# IronBen.net
KiCad netlist of a schematic drawn in EasyEDA Pro
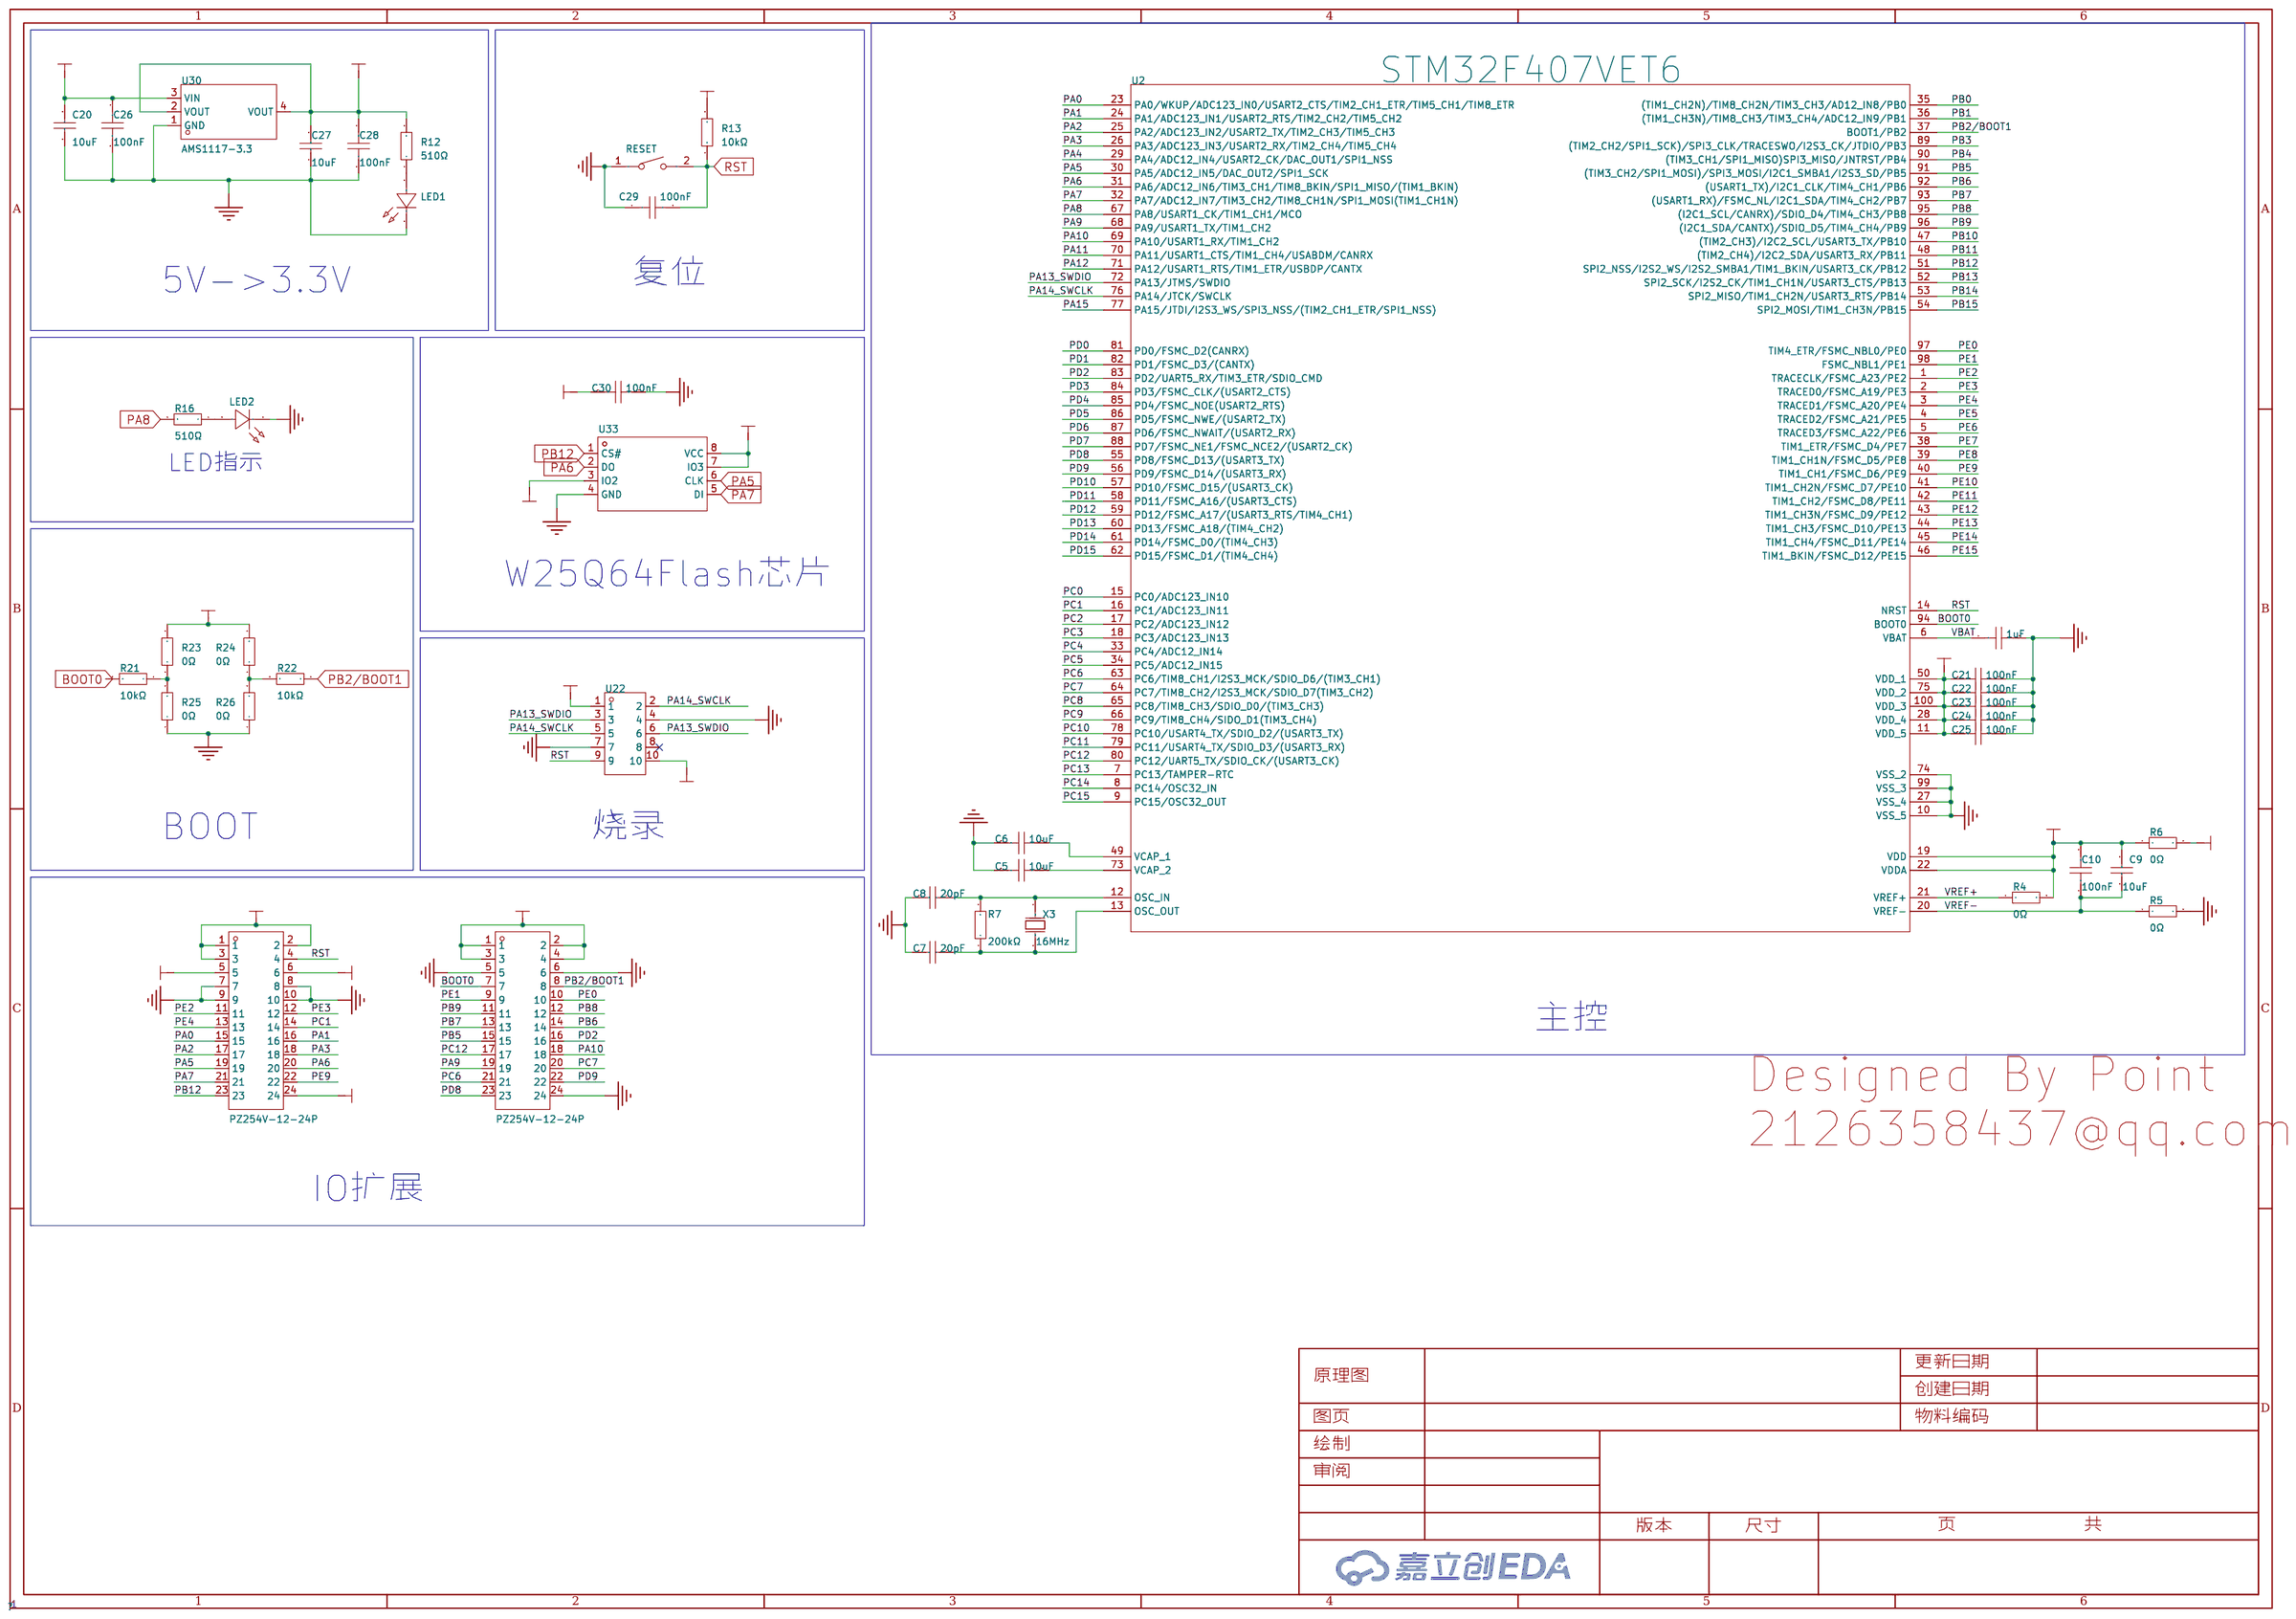
[diagram p0: schematic sheet]

(export (version "E")
  (design (tool "Eeschema 10.0.6"))
  (components
    (comp (ref "C5")
      (value "10uF")
      (footprint "easyedapro:C0603")
      (description "容值:10uF;精度:±10%;额定电压:10V;材质(温度系数):X5R;")
      (fields
        (field (name "Manufacturer Part") "CL10A106KP8NNNC")
        (field (name "Manufacturer") "SAMSUNG(三星)")
      )
      (libsource (lib "easyedapro") (part "CL10A106KP8NNNC"))
    )
    (comp (ref "C6")
      (value "10uF")
      (footprint "easyedapro:C0603")
      (description "容值:10uF;精度:±10%;额定电压:10V;材质(温度系数):X5R;")
      (fields
        (field (name "Manufacturer Part") "CL10A106KP8NNNC")
        (field (name "Manufacturer") "SAMSUNG(三星)")
      )
      (libsource (lib "easyedapro") (part "CL10A106KP8NNNC"))
    )
    (comp (ref "C7")
      (value "20pF")
      (footprint "easyedapro:C0603")
      (description "容值:20pF;精度:±5%;额定电压:50V;材质(温度系数):C0G;")
      (fields
        (field (name "Manufacturer Part") "CL10C200JB8NNNC")
        (field (name "Manufacturer") "SAMSUNG(三星)")
      )
      (libsource (lib "easyedapro") (part "CL10C200JB8NNNC"))
    )
    (comp (ref "C8")
      (value "20pF")
      (footprint "easyedapro:C0603")
      (description "容值:20pF;精度:±5%;额定电压:50V;材质(温度系数):C0G;")
      (fields
        (field (name "Manufacturer Part") "CL10C200JB8NNNC")
        (field (name "Manufacturer") "SAMSUNG(三星)")
      )
      (libsource (lib "easyedapro") (part "CL10C200JB8NNNC"))
    )
    (comp (ref "C9")
      (value "10uF")
      (footprint "easyedapro:C0805")
      (description "容值:10uF;精度:±10%;额定电压:10V;材质(温度系数):X5R;")
      (fields
        (field (name "Manufacturer Part") "CL21A106KPFNNNE")
        (field (name "Manufacturer") "SAMSUNG(三星)")
      )
      (libsource (lib "easyedapro") (part "CL21A106KPFNNNE"))
    )
    (comp (ref "C10")
      (value "100nF")
      (footprint "easyedapro:C0603")
      (description "容值:100nF;精度:±10%;额定电压:50V;材质(温度系数):X7R;")
      (fields
        (field (name "Manufacturer Part") "CC0603KRX7R9BB104")
        (field (name "Manufacturer") "YAGEO(国巨)")
      )
      (libsource (lib "easyedapro") (part "CC0603KRX7R9BB104"))
    )
    (comp (ref "C11")
      (value "1uF")
      (footprint "easyedapro:C0603")
      (description "容值:1uF;精度:±10%;额定电压:50V;材质(温度系数):X5R;")
      (fields
        (field (name "Manufacturer Part") "CL10A105KB8NNNC")
        (field (name "Manufacturer") "SAMSUNG(三星)")
      )
      (libsource (lib "easyedapro") (part "CL10A105KB8NNNC"))
    )
    (comp (ref "C20")
      (value "10uF")
      (footprint "easyedapro:C0805")
      (description "容值:10uF;精度:±10%;额定电压:10V;材质(温度系数):X5R;")
      (fields
        (field (name "Manufacturer Part") "CL21A106KPFNNNE")
        (field (name "Manufacturer") "SAMSUNG(三星)")
      )
      (libsource (lib "easyedapro") (part "CL21A106KPFNNNE"))
    )
    (comp (ref "C21")
      (value "100nF")
      (footprint "easyedapro:C0603")
      (description "容值:100nF;精度:±10%;额定电压:50V;材质(温度系数):X7R;")
      (fields
        (field (name "Manufacturer Part") "CC0603KRX7R9BB104")
        (field (name "Manufacturer") "YAGEO(国巨)")
      )
      (libsource (lib "easyedapro") (part "CC0603KRX7R9BB104"))
    )
    (comp (ref "C22")
      (value "100nF")
      (footprint "easyedapro:C0603")
      (description "容值:100nF;精度:±10%;额定电压:50V;材质(温度系数):X7R;")
      (fields
        (field (name "Manufacturer Part") "CC0603KRX7R9BB104")
        (field (name "Manufacturer") "YAGEO(国巨)")
      )
      (libsource (lib "easyedapro") (part "CC0603KRX7R9BB104"))
    )
    (comp (ref "C23")
      (value "100nF")
      (footprint "easyedapro:C0603")
      (description "容值:100nF;精度:±10%;额定电压:50V;材质(温度系数):X7R;")
      (fields
        (field (name "Manufacturer Part") "CC0603KRX7R9BB104")
        (field (name "Manufacturer") "YAGEO(国巨)")
      )
      (libsource (lib "easyedapro") (part "CC0603KRX7R9BB104"))
    )
    (comp (ref "C24")
      (value "100nF")
      (footprint "easyedapro:C0603")
      (description "容值:100nF;精度:±10%;额定电压:50V;材质(温度系数):X7R;")
      (fields
        (field (name "Manufacturer Part") "CC0603KRX7R9BB104")
        (field (name "Manufacturer") "YAGEO(国巨)")
      )
      (libsource (lib "easyedapro") (part "CC0603KRX7R9BB104"))
    )
    (comp (ref "C25")
      (value "100nF")
      (footprint "easyedapro:C0603")
      (description "容值:100nF;精度:±10%;额定电压:50V;材质(温度系数):X7R;")
      (fields
        (field (name "Manufacturer Part") "CC0603KRX7R9BB104")
        (field (name "Manufacturer") "YAGEO(国巨)")
      )
      (libsource (lib "easyedapro") (part "CC0603KRX7R9BB104"))
    )
    (comp (ref "C26")
      (value "100nF")
      (footprint "easyedapro:C0603")
      (description "容值:100nF;精度:±10%;额定电压:50V;材质(温度系数):X7R;")
      (fields
        (field (name "Manufacturer Part") "CC0603KRX7R9BB104")
        (field (name "Manufacturer") "YAGEO(国巨)")
      )
      (libsource (lib "easyedapro") (part "CC0603KRX7R9BB104"))
    )
    (comp (ref "C27")
      (value "10uF")
      (footprint "easyedapro:C0805")
      (description "容值:10uF;精度:±10%;额定电压:10V;材质(温度系数):X5R;")
      (fields
        (field (name "Manufacturer Part") "CL21A106KPFNNNE")
        (field (name "Manufacturer") "SAMSUNG(三星)")
      )
      (libsource (lib "easyedapro") (part "CL21A106KPFNNNE"))
    )
    (comp (ref "C28")
      (value "100nF")
      (footprint "easyedapro:C0603")
      (description "容值:100nF;精度:±10%;额定电压:50V;材质(温度系数):X7R;")
      (fields
        (field (name "Manufacturer Part") "CC0603KRX7R9BB104")
        (field (name "Manufacturer") "YAGEO(国巨)")
      )
      (libsource (lib "easyedapro") (part "CC0603KRX7R9BB104"))
    )
    (comp (ref "C29")
      (value "100nF")
      (footprint "easyedapro:C0603")
      (description "容值:100nF;精度:±10%;额定电压:50V;材质(温度系数):X7R;")
      (fields
        (field (name "Manufacturer Part") "CC0603KRX7R9BB104")
        (field (name "Manufacturer") "YAGEO(国巨)")
      )
      (libsource (lib "easyedapro") (part "CC0603KRX7R9BB104"))
    )
    (comp (ref "C30")
      (value "100nF")
      (footprint "easyedapro:C0603")
      (description "容值:100nF;精度:±10%;额定电压:50V;材质(温度系数):X7R;")
      (fields
        (field (name "Manufacturer Part") "CC0603KRX7R9BB104")
        (field (name "Manufacturer") "YAGEO(国巨)")
      )
      (libsource (lib "easyedapro") (part "CC0603KRX7R9BB104"))
    )
    (comp (ref "H6")
      (value "PZ254V-12-24P")
      (footprint "easyedapro:HDR-TH_24P-P2.54-V-M-R2-C12-S2.54")
      (fields (field (name "Manufacturer") "XFCN(兴飞)"))
      (libsource (lib "easyedapro") (part "PZ254V-12-24P"))
    )
    (comp (ref "H7")
      (value "PZ254V-12-24P")
      (footprint "easyedapro:HDR-TH_24P-P2.54-V-M-R2-C12-S2.54")
      (fields (field (name "Manufacturer") "XFCN(兴飞)"))
      (libsource (lib "easyedapro") (part "PZ254V-12-24P"))
    )
    (comp (ref "LED1")
      (value "XL-1608SURC-06")
      (footprint "easyedapro:LED0603-RD_RED")
      (description "发光颜色:红色;功率:55mW;正向电流:25mA;主波长:617nm~621nm;透镜颜色:无色透明透镜;色温:-;发光角度:120°;载带方式:正贴;工作温度:-30°C~+85°C;")
      (fields (field (name "Manufacturer") "XINGLIGHT(成兴光)"))
      (libsource (lib "easyedapro") (part "XL-1608SURC-06"))
    )
    (comp (ref "LED2")
      (value "XL-1608SURC-06")
      (footprint "easyedapro:LED0603-RD_RED")
      (description "发光颜色:红色;功率:55mW;正向电流:25mA;主波长:617nm~621nm;透镜颜色:无色透明透镜;色温:-;发光角度:120°;载带方式:正贴;工作温度:-30°C~+85°C;")
      (fields (field (name "Manufacturer") "XINGLIGHT(成兴光)"))
      (libsource (lib "easyedapro") (part "XL-1608SURC-06"))
    )
    (comp (ref "R4")
      (value "0Ω")
      (footprint "easyedapro:R0603")
      (description "电阻类型:厚膜电阻;阻值:0Ω;精度:±1%;功率:100mW;最大工作电压:75V;")
      (fields
        (field (name "Manufacturer Part") "0603WAF0000T5E")
        (field (name "Manufacturer") "UNI-ROYAL(厚声)")
      )
      (libsource (lib "easyedapro") (part "0603WAF0000T5E"))
    )
    (comp (ref "R5")
      (value "0Ω")
      (footprint "easyedapro:R0603")
      (description "电阻类型:厚膜电阻;阻值:0Ω;精度:±1%;功率:100mW;最大工作电压:75V;")
      (fields
        (field (name "Manufacturer Part") "0603WAF0000T5E")
        (field (name "Manufacturer") "UNI-ROYAL(厚声)")
      )
      (libsource (lib "easyedapro") (part "0603WAF0000T5E"))
    )
    (comp (ref "R6")
      (value "0Ω")
      (footprint "easyedapro:R0603")
      (description "电阻类型:厚膜电阻;阻值:0Ω;精度:±1%;功率:100mW;最大工作电压:75V;")
      (fields
        (field (name "Manufacturer Part") "0603WAF0000T5E")
        (field (name "Manufacturer") "UNI-ROYAL(厚声)")
      )
      (libsource (lib "easyedapro") (part "0603WAF0000T5E"))
    )
    (comp (ref "R7")
      (value "200kΩ")
      (footprint "easyedapro:R0603")
      (description "电阻类型:厚膜电阻;阻值:200kΩ;精度:±1%;功率:100mW;最大工作电压:75V;温度系数:±100ppm/°C;")
      (fields
        (field (name "Manufacturer Part") "0603WAF2003T5E")
        (field (name "Manufacturer") "UNI-ROYAL(厚声)")
      )
      (libsource (lib "easyedapro") (part "0603WAF2003T5E"))
    )
    (comp (ref "R12")
      (value "510Ω")
      (footprint "easyedapro:R0603")
      (description "电阻类型:厚膜电阻;阻值:510Ω;精度:±1%;功率:100mW;最大工作电压:75V;温度系数:±100ppm/°C;")
      (fields
        (field (name "Manufacturer Part") "0603WAF5100T5E")
        (field (name "Manufacturer") "UNI-ROYAL(厚声)")
      )
      (libsource (lib "easyedapro") (part "0603WAF5100T5E"))
    )
    (comp (ref "R13")
      (value "10kΩ")
      (footprint "easyedapro:R0603")
      (description "电阻类型:厚膜电阻;阻值:10kΩ;精度:±1%;功率:100mW;最大工作电压:75V;温度系数:±100ppm/°C;")
      (fields
        (field (name "Manufacturer Part") "0603WAF1002T5E")
        (field (name "Manufacturer") "UNI-ROYAL(厚声)")
      )
      (libsource (lib "easyedapro") (part "0603WAF1002T5E"))
    )
    (comp (ref "R16")
      (value "510Ω")
      (footprint "easyedapro:R0603")
      (description "电阻类型:厚膜电阻;阻值:510Ω;精度:±1%;功率:100mW;最大工作电压:75V;温度系数:±100ppm/°C;")
      (fields
        (field (name "Manufacturer Part") "0603WAF5100T5E")
        (field (name "Manufacturer") "UNI-ROYAL(厚声)")
      )
      (libsource (lib "easyedapro") (part "0603WAF5100T5E"))
    )
    (comp (ref "R21")
      (value "10kΩ")
      (footprint "easyedapro:R0603")
      (description "电阻类型:厚膜电阻;阻值:10kΩ;精度:±1%;功率:100mW;最大工作电压:75V;温度系数:±100ppm/°C;")
      (fields
        (field (name "Manufacturer Part") "0603WAF1002T5E")
        (field (name "Manufacturer") "UNI-ROYAL(厚声)")
      )
      (libsource (lib "easyedapro") (part "0603WAF1002T5E"))
    )
    (comp (ref "R22")
      (value "10kΩ")
      (footprint "easyedapro:R0603")
      (description "电阻类型:厚膜电阻;阻值:10kΩ;精度:±1%;功率:100mW;最大工作电压:75V;温度系数:±100ppm/°C;")
      (fields
        (field (name "Manufacturer Part") "0603WAF1002T5E")
        (field (name "Manufacturer") "UNI-ROYAL(厚声)")
      )
      (libsource (lib "easyedapro") (part "0603WAF1002T5E"))
    )
    (comp (ref "R23")
      (value "0Ω")
      (footprint "easyedapro:R0603")
      (description "电阻类型:厚膜电阻;阻值:0Ω;精度:±1%;功率:100mW;最大工作电压:75V;")
      (fields
        (field (name "Manufacturer Part") "0603WAF0000T5E")
        (field (name "Manufacturer") "UNI-ROYAL(厚声)")
      )
      (libsource (lib "easyedapro") (part "0603WAF0000T5E"))
    )
    (comp (ref "R24")
      (value "0Ω")
      (footprint "easyedapro:R0603")
      (description "电阻类型:厚膜电阻;阻值:0Ω;精度:±1%;功率:100mW;最大工作电压:75V;")
      (fields
        (field (name "Manufacturer Part") "0603WAF0000T5E")
        (field (name "Manufacturer") "UNI-ROYAL(厚声)")
      )
      (libsource (lib "easyedapro") (part "0603WAF0000T5E"))
    )
    (comp (ref "R25")
      (value "0Ω")
      (footprint "easyedapro:R0603")
      (description "电阻类型:厚膜电阻;阻值:0Ω;精度:±1%;功率:100mW;最大工作电压:75V;")
      (fields
        (field (name "Manufacturer Part") "0603WAF0000T5E")
        (field (name "Manufacturer") "UNI-ROYAL(厚声)")
      )
      (libsource (lib "easyedapro") (part "0603WAF0000T5E"))
    )
    (comp (ref "R26")
      (value "0Ω")
      (footprint "easyedapro:R0603")
      (description "电阻类型:厚膜电阻;阻值:0Ω;精度:±1%;功率:100mW;最大工作电压:75V;")
      (fields
        (field (name "Manufacturer Part") "0603WAF0000T5E")
        (field (name "Manufacturer") "UNI-ROYAL(厚声)")
      )
      (libsource (lib "easyedapro") (part "0603WAF0000T5E"))
    )
    (comp (ref "RESET")
      (value "TS-1088-AR02016")
      (footprint "easyedapro:SW-SMD_L3.9-W3.0-P4.45")
      (fields (field (name "Manufacturer") "XUNPU(讯普)"))
      (libsource (lib "easyedapro") (part "TS-1088-AR02016"))
    )
    (comp (ref "U2")
      (value "STM32F407VET6")
      (footprint "easyedapro:LQFP-100_L14.0-W14.0-P0.50-LS16.0-BL")
      (fields (field (name "Manufacturer") "ST"))
      (libsource (lib "easyedapro") (part "STM32F407VET6"))
    )
    (comp (ref "U22")
      (value "ZX-PZ2.54-2-5PZZ")
      (footprint "easyedapro:HDR-TH_10P-P2.54-V-M-R2-C5-S2.54")
      (fields (field (name "Manufacturer") "Megastar(兆星)"))
      (libsource (lib "easyedapro") (part "ZX-PZ2.54-2-5PZZ"))
    )
    (comp (ref "U30")
      (value "AMS1117-3.3")
      (footprint "easyedapro:SOT-223-3_L6.5-W3.4-P2.30-LS7.0-BR")
      (description "输出类型:固定;最大输入电压:-;输出电压:3.3V;最大输出电流:1A;电源纹波抑制比(PSRR):72dB@(120Hz);输出极性:正极;")
      (fields (field (name "Manufacturer") "AMS"))
      (libsource (lib "easyedapro") (part "AMS1117-3.3"))
    )
    (comp (ref "U33")
      (value "W25Q64JVSSIQ")
      (footprint "easyedapro:SOP-8_L5.3-W5.3-P1.27-LS8.0-BL")
      (description "64M-bit/8M-byte FLASH芯片,SPI接口 133MHz(266/532MHz Dual/Quad-SPI) 比W25Q64FVSSIG更高速度")
      (fields (field (name "Manufacturer") "WINBOND(华邦)"))
      (libsource (lib "easyedapro") (part "W25Q64JVSSIQ"))
    )
    (comp (ref "X3")
      (value "16MHz")
      (footprint "easyedapro:OSC-TH_L10.0-W4.5-P5.00")
      (description "晶振类型:直插晶振;频率:16MHz;常温频差:±20ppm;外接负载电容:20pF;频率稳定度(全温):±30ppm;")
      (fields (field (name "Manufacturer Part") "X49SD16MSD2SC") (field (name "Manufacturer") "YXC(扬兴晶振)"))
      (libsource (lib "easyedapro") (part "X49SD16MSD2SC"))
    )
  )
  (nets
    (net (code "1") (name "/PA0") (class "Default")
      (node (ref "H6") (pin "15") (pinfunction "15_15") (pintype "unspecified"))
      (node (ref "U2") (pin "23") (pinfunction "PA0/WKUP/ADC123_IN0/USART2_CTS/TIM2_CH1_ETR/TIM5_CH1/TIM8_ETR_23") (pintype "input"))
    )
    (net (code "2") (name "/PA1") (class "Default")
      (node (ref "H6") (pin "16") (pinfunction "16_16") (pintype "unspecified"))
      (node (ref "U2") (pin "24") (pinfunction "PA1/ADC123_IN1/USART2_RTS/TIM2_CH2/TIM5_CH2_24") (pintype "input"))
    )
    (net (code "3") (name "/PA2") (class "Default")
      (node (ref "H6") (pin "17") (pinfunction "17_17") (pintype "unspecified"))
      (node (ref "U2") (pin "25") (pinfunction "PA2/ADC123_IN2/USART2_TX/TIM2_CH3/TIM5_CH3_25") (pintype "input"))
    )
    (net (code "4") (name "/PA3") (class "Default")
      (node (ref "H6") (pin "18") (pinfunction "18_18") (pintype "unspecified"))
      (node (ref "U2") (pin "26") (pinfunction "PA3/ADC123_IN3/USART2_RX/TIM2_CH4/TIM5_CH4_26") (pintype "input"))
    )
    (net (code "5") (name "/PA4") (class "Default")
      (node (ref "U2") (pin "29") (pinfunction "PA4/ADC12_IN4/USART2_CK/DAC_OUT1/SPI1_NSS_29") (pintype "input"))
    )
    (net (code "6") (name "/PA9") (class "Default")
      (node (ref "H7") (pin "19") (pinfunction "19_19") (pintype "unspecified"))
      (node (ref "U2") (pin "68") (pinfunction "PA9/USART1_TX/TIM1_CH2_68") (pintype "input"))
    )
    (net (code "7") (name "/PA10") (class "Default")
      (node (ref "H7") (pin "18") (pinfunction "18_18") (pintype "unspecified"))
      (node (ref "U2") (pin "69") (pinfunction "PA10/USART1_RX/TIM1_CH2_69") (pintype "input"))
    )
    (net (code "8") (name "/PA11") (class "Default")
      (node (ref "U2") (pin "70") (pinfunction "PA11/USART1_CTS/TIM1_CH4/USABDM/CANRX_70") (pintype "input"))
    )
    (net (code "9") (name "/PA12") (class "Default")
      (node (ref "U2") (pin "71") (pinfunction "PA12/USART1_RTS/TIM1_ETR/USBDP/CANTX_71") (pintype "input"))
    )
    (net (code "10") (name "/PA13_SWDIO") (class "Default")
      (node (ref "U2") (pin "72") (pinfunction "PA13/JTMS/SWDIO_72") (pintype "input"))
      (node (ref "U22") (pin "3") (pinfunction "3_3") (pintype "unspecified"))
      (node (ref "U22") (pin "6") (pinfunction "6_6") (pintype "unspecified"))
    )
    (net (code "11") (name "/PA14_SWCLK") (class "Default")
      (node (ref "U2") (pin "76") (pinfunction "PA14/JTCK/SWCLK_76") (pintype "input"))
      (node (ref "U22") (pin "2") (pinfunction "2_2") (pintype "unspecified"))
      (node (ref "U22") (pin "5") (pinfunction "5_5") (pintype "unspecified"))
    )
    (net (code "12") (name "/PA15") (class "Default")
      (node (ref "U2") (pin "77") (pinfunction "PA15/JTDI/I2S3_WS/SPI3_NSS/(TIM2_CH1_ETR/SPI1_NSS)_77") (pintype "input"))
    )
    (net (code "13") (name "/PB0") (class "Default")
      (node (ref "U2") (pin "35") (pinfunction "(TIM1_CH2N)/TIM8_CH2N/TIM3_CH3/AD12_IN8/PB0_35") (pintype "input"))
    )
    (net (code "14") (name "/PB1") (class "Default")
      (node (ref "U2") (pin "36") (pinfunction "(TIM1_CH3N)/TIM8_CH3/TIM3_CH4/ADC12_IN9/PB1_36") (pintype "input"))
    )
    (net (code "15") (name "/PB3") (class "Default")
      (node (ref "U2") (pin "89") (pinfunction "(TIM2_CH2/SPI1_SCK)/SPI3_CLK/TRACESWO/I2S3_CK/JTDIO/PB3_89") (pintype "input"))
    )
    (net (code "16") (name "/PB4") (class "Default")
      (node (ref "U2") (pin "90") (pinfunction "(TIM3_CH1/SPI1_MISO)SPI3_MISO/JNTRST/PB4_90") (pintype "input"))
    )
    (net (code "17") (name "/PB5") (class "Default")
      (node (ref "H7") (pin "15") (pinfunction "15_15") (pintype "unspecified"))
      (node (ref "U2") (pin "91") (pinfunction "(TIM3_CH2/SPI1_MOSI)/SPI3_MOSI/I2C1_SMBA1/I2S3_SD/PB5_91") (pintype "input"))
    )
    (net (code "18") (name "/PB6") (class "Default")
      (node (ref "H7") (pin "14") (pinfunction "14_14") (pintype "unspecified"))
      (node (ref "U2") (pin "92") (pinfunction "(USART1_TX)/I2C1_CLK/TIM4_CH1/PB6_92") (pintype "input"))
    )
    (net (code "19") (name "/PB7") (class "Default")
      (node (ref "H7") (pin "13") (pinfunction "13_13") (pintype "unspecified"))
      (node (ref "U2") (pin "93") (pinfunction "(USART1_RX)/FSMC_NL/I2C1_SDA/TIM4_CH2/PB7_93") (pintype "input"))
    )
    (net (code "20") (name "/PB8") (class "Default")
      (node (ref "H7") (pin "12") (pinfunction "12_12") (pintype "unspecified"))
      (node (ref "U2") (pin "95") (pinfunction "(I2C1_SCL/CANRX)/SDIO_D4/TIM4_CH3/PB8_95") (pintype "input"))
    )
    (net (code "21") (name "/PB9") (class "Default")
      (node (ref "H7") (pin "11") (pinfunction "11_11") (pintype "unspecified"))
      (node (ref "U2") (pin "96") (pinfunction "(I2C1_SDA/CANTX)/SDIO_D5/TIM4_CH4/PB9_96") (pintype "input"))
    )
    (net (code "22") (name "/PB10") (class "Default")
      (node (ref "U2") (pin "47") (pinfunction "(TIM2_CH3)/I2C2_SCL/USART3_TX/PB10_47") (pintype "input"))
    )
    (net (code "23") (name "/PB11") (class "Default")
      (node (ref "U2") (pin "48") (pinfunction "(TIM2_CH4)/I2C2_SDA/USART3_RX/PB11_48") (pintype "input"))
    )
    (net (code "24") (name "/PB13") (class "Default")
      (node (ref "U2") (pin "52") (pinfunction "SPI2_SCK/I2S2_CK/TIM1_CH1N/USART3_CTS/PB13_52") (pintype "input"))
    )
    (net (code "25") (name "/PB14") (class "Default")
      (node (ref "U2") (pin "53") (pinfunction "SPI2_MISO/TIM1_CH2N/USART3_RTS/PB14_53") (pintype "input"))
    )
    (net (code "26") (name "/PB15") (class "Default")
      (node (ref "U2") (pin "54") (pinfunction "SPI2_MOSI/TIM1_CH3N/PB15_54") (pintype "input"))
    )
    (net (code "27") (name "/PC0") (class "Default")
      (node (ref "U2") (pin "15") (pinfunction "PC0/ADC123_IN10_15") (pintype "input"))
    )
    (net (code "28") (name "/PC1") (class "Default")
      (node (ref "H6") (pin "14") (pinfunction "14_14") (pintype "unspecified"))
      (node (ref "U2") (pin "16") (pinfunction "PC1/ADC123_IN11_16") (pintype "input"))
    )
    (net (code "29") (name "/PC2") (class "Default")
      (node (ref "U2") (pin "17") (pinfunction "PC2/ADC123_IN12_17") (pintype "input"))
    )
    (net (code "30") (name "/PC3") (class "Default")
      (node (ref "U2") (pin "18") (pinfunction "PC3/ADC123_IN13_18") (pintype "input"))
    )
    (net (code "31") (name "/PC4") (class "Default")
      (node (ref "U2") (pin "33") (pinfunction "PC4/ADC12_IN14_33") (pintype "input"))
    )
    (net (code "32") (name "/PC5") (class "Default")
      (node (ref "U2") (pin "34") (pinfunction "PC5/ADC12_IN15_34") (pintype "input"))
    )
    (net (code "33") (name "/PC6") (class "Default")
      (node (ref "H7") (pin "21") (pinfunction "21_21") (pintype "unspecified"))
      (node (ref "U2") (pin "63") (pinfunction "PC6/TIM8_CH1/I2S3_MCK/SDIO_D6/(TIM3_CH1)_63") (pintype "input"))
    )
    (net (code "34") (name "/PC7") (class "Default")
      (node (ref "H7") (pin "20") (pinfunction "20_20") (pintype "unspecified"))
      (node (ref "U2") (pin "64") (pinfunction "PC7/TIM8_CH2/I2S3_MCK/SDIO_D7(TIM3_CH2)_64") (pintype "input"))
    )
    (net (code "35") (name "/PC8") (class "Default")
      (node (ref "U2") (pin "65") (pinfunction "PC8/TIM8_CH3/SDIO_D0/(TIM3_CH3)_65") (pintype "input"))
    )
    (net (code "36") (name "/PC9") (class "Default")
      (node (ref "U2") (pin "66") (pinfunction "PC9/TIM8_CH4/SIDO_D1(TIM3_CH4)_66") (pintype "input"))
    )
    (net (code "37") (name "/PC10") (class "Default")
      (node (ref "U2") (pin "78") (pinfunction "PC10/USART4_TX/SDIO_D2/(USART3_TX)_78") (pintype "input"))
    )
    (net (code "38") (name "/PC11") (class "Default")
      (node (ref "U2") (pin "79") (pinfunction "PC11/USART4_TX/SDIO_D3/(USART3_RX)_79") (pintype "input"))
    )
    (net (code "39") (name "/PC12") (class "Default")
      (node (ref "H7") (pin "17") (pinfunction "17_17") (pintype "unspecified"))
      (node (ref "U2") (pin "80") (pinfunction "PC12/UART5_TX/SDIO_CK/(USART3_CK)_80") (pintype "input"))
    )
    (net (code "40") (name "/PC13") (class "Default")
      (node (ref "U2") (pin "7") (pinfunction "PC13/TAMPER-RTC_7") (pintype "input"))
    )
    (net (code "41") (name "/PC14") (class "Default")
      (node (ref "U2") (pin "8") (pinfunction "PC14/OSC32_IN_8") (pintype "input"))
    )
    (net (code "42") (name "/PC15") (class "Default")
      (node (ref "U2") (pin "9") (pinfunction "PC15/OSC32_OUT_9") (pintype "input"))
    )
    (net (code "43") (name "/PD0") (class "Default")
      (node (ref "U2") (pin "81") (pinfunction "PD0/FSMC_D2(CANRX)_81") (pintype "input"))
    )
    (net (code "44") (name "/PD1") (class "Default")
      (node (ref "U2") (pin "82") (pinfunction "PD1/FSMC_D3/(CANTX)_82") (pintype "input"))
    )
    (net (code "45") (name "/PD2") (class "Default")
      (node (ref "H7") (pin "16") (pinfunction "16_16") (pintype "unspecified"))
      (node (ref "U2") (pin "83") (pinfunction "PD2/UART5_RX/TIM3_ETR/SDIO_CMD_83") (pintype "input"))
    )
    (net (code "46") (name "/PD3") (class "Default")
      (node (ref "U2") (pin "84") (pinfunction "PD3/FSMC_CLK/(USART2_CTS)_84") (pintype "input"))
    )
    (net (code "47") (name "/PD4") (class "Default")
      (node (ref "U2") (pin "85") (pinfunction "PD4/FSMC_NOE(USART2_RTS)_85") (pintype "input"))
    )
    (net (code "48") (name "/PD5") (class "Default")
      (node (ref "U2") (pin "86") (pinfunction "PD5/FSMC_NWE/(USART2_TX)_86") (pintype "input"))
    )
    (net (code "49") (name "/PD6") (class "Default")
      (node (ref "U2") (pin "87") (pinfunction "PD6/FSMC_NWAIT/(USART2_RX)_87") (pintype "input"))
    )
    (net (code "50") (name "/PD7") (class "Default")
      (node (ref "U2") (pin "88") (pinfunction "PD7/FSMC_NE1/FSMC_NCE2/(USART2_CK)_88") (pintype "input"))
    )
    (net (code "51") (name "/PD8") (class "Default")
      (node (ref "H7") (pin "23") (pinfunction "23_23") (pintype "unspecified"))
      (node (ref "U2") (pin "55") (pinfunction "PD8/FSMC_D13/(USART3_TX)_55") (pintype "input"))
    )
    (net (code "52") (name "/PD9") (class "Default")
      (node (ref "H7") (pin "22") (pinfunction "22_22") (pintype "unspecified"))
      (node (ref "U2") (pin "56") (pinfunction "PD9/FSMC_D14/(USART3_RX)_56") (pintype "input"))
    )
    (net (code "53") (name "/PD10") (class "Default")
      (node (ref "U2") (pin "57") (pinfunction "PD10/FSMC_D15/(USART3_CK)_57") (pintype "input"))
    )
    (net (code "54") (name "/PD11") (class "Default")
      (node (ref "U2") (pin "58") (pinfunction "PD11/FSMC_A16/(USART3_CTS)_58") (pintype "input"))
    )
    (net (code "55") (name "/PD12") (class "Default")
      (node (ref "U2") (pin "59") (pinfunction "PD12/FSMC_A17/(USART3_RTS/TIM4_CH1)_59") (pintype "input"))
    )
    (net (code "56") (name "/PD13") (class "Default")
      (node (ref "U2") (pin "60") (pinfunction "PD13/FSMC_A18/(TIM4_CH2)_60") (pintype "input"))
    )
    (net (code "57") (name "/PD14") (class "Default")
      (node (ref "U2") (pin "61") (pinfunction "PD14/FSMC_D0/(TIM4_CH3)_61") (pintype "input"))
    )
    (net (code "58") (name "/PD15") (class "Default")
      (node (ref "U2") (pin "62") (pinfunction "PD15/FSMC_D1/(TIM4_CH4)_62") (pintype "input"))
    )
    (net (code "59") (name "/PE0") (class "Default")
      (node (ref "H7") (pin "10") (pinfunction "10_10") (pintype "unspecified"))
      (node (ref "U2") (pin "97") (pinfunction "TIM4_ETR/FSMC_NBL0/PE0_97") (pintype "input"))
    )
    (net (code "60") (name "/PE1") (class "Default")
      (node (ref "H7") (pin "9") (pinfunction "9_9") (pintype "unspecified"))
      (node (ref "U2") (pin "98") (pinfunction "FSMC_NBL1/PE1_98") (pintype "input"))
    )
    (net (code "61") (name "/PE2") (class "Default")
      (node (ref "H6") (pin "11") (pinfunction "11_11") (pintype "unspecified"))
      (node (ref "U2") (pin "1") (pinfunction "TRACECLK/FSMC_A23/PE2_1") (pintype "input"))
    )
    (net (code "62") (name "/PE3") (class "Default")
      (node (ref "H6") (pin "12") (pinfunction "12_12") (pintype "unspecified"))
      (node (ref "U2") (pin "2") (pinfunction "TRACED0/FSMC_A19/PE3_2") (pintype "input"))
    )
    (net (code "63") (name "/PE4") (class "Default")
      (node (ref "H6") (pin "13") (pinfunction "13_13") (pintype "unspecified"))
      (node (ref "U2") (pin "3") (pinfunction "TRACED1/FSMC_A20/PE4_3") (pintype "input"))
    )
    (net (code "64") (name "/PE5") (class "Default")
      (node (ref "U2") (pin "4") (pinfunction "TRACED2/FSMC_A21/PE5_4") (pintype "input"))
    )
    (net (code "65") (name "/PE6") (class "Default")
      (node (ref "U2") (pin "5") (pinfunction "TRACED3/FSMC_A22/PE6_5") (pintype "input"))
    )
    (net (code "66") (name "/PE7") (class "Default")
      (node (ref "U2") (pin "38") (pinfunction "TIM1_ETR/FSMC_D4/PE7_38") (pintype "input"))
    )
    (net (code "67") (name "/PE8") (class "Default")
      (node (ref "U2") (pin "39") (pinfunction "TIM1_CH1N/FSMC_D5/PE8_39") (pintype "input"))
    )
    (net (code "68") (name "/PE9") (class "Default")
      (node (ref "H6") (pin "22") (pinfunction "22_22") (pintype "unspecified"))
      (node (ref "U2") (pin "40") (pinfunction "TIM1_CH1/FSMC_D6/PE9_40") (pintype "input"))
    )
    (net (code "69") (name "/PE10") (class "Default")
      (node (ref "U2") (pin "41") (pinfunction "TIM1_CH2N/FSMC_D7/PE10_41") (pintype "input"))
    )
    (net (code "70") (name "/PE11") (class "Default")
      (node (ref "U2") (pin "42") (pinfunction "TIM1_CH2/FSMC_D8/PE11_42") (pintype "input"))
    )
    (net (code "71") (name "/PE12") (class "Default")
      (node (ref "U2") (pin "43") (pinfunction "TIM1_CH3N/FSMC_D9/PE12_43") (pintype "input"))
    )
    (net (code "72") (name "/PE13") (class "Default")
      (node (ref "U2") (pin "44") (pinfunction "TIM1_CH3/FSMC_D10/PE13_44") (pintype "input"))
    )
    (net (code "73") (name "/PE14") (class "Default")
      (node (ref "U2") (pin "45") (pinfunction "TIM1_CH4/FSMC_D11/PE14_45") (pintype "input"))
    )
    (net (code "74") (name "/PE15") (class "Default")
      (node (ref "U2") (pin "46") (pinfunction "TIM1_BKIN/FSMC_D12/PE15_46") (pintype "input"))
    )
    (net (code "75") (name "/VBAT") (class "Default")
      (node (ref "C11") (pin "1") (pinfunction "1_1") (pintype "unspecified"))
      (node (ref "U2") (pin "6") (pinfunction "VBAT_6") (pintype "input"))
    )
    (net (code "76") (name "/VREF+") (class "Default")
      (node (ref "R4") (pin "1") (pinfunction "1_1") (pintype "input"))
      (node (ref "U2") (pin "21") (pinfunction "VREF+_21") (pintype "input"))
    )
    (net (code "77") (name "/VREF-") (class "Default")
      (node (ref "C10") (pin "1") (pinfunction "1_1") (pintype "unspecified"))
      (node (ref "C9") (pin "1") (pinfunction "1_1") (pintype "input"))
      (node (ref "R5") (pin "1") (pinfunction "1_1") (pintype "input"))
      (node (ref "U2") (pin "20") (pinfunction "VREF-_20") (pintype "input"))
    )
    (net (code "78") (name "3V3") (class "Default")
      (node (ref "C21") (pin "2") (pinfunction "2_2") (pintype "unspecified"))
      (node (ref "C22") (pin "2") (pinfunction "2_2") (pintype "unspecified"))
      (node (ref "C23") (pin "2") (pinfunction "2_2") (pintype "unspecified"))
      (node (ref "C24") (pin "2") (pinfunction "2_2") (pintype "unspecified"))
      (node (ref "C25") (pin "2") (pinfunction "2_2") (pintype "unspecified"))
      (node (ref "C27") (pin "2") (pinfunction "2_2") (pintype "input"))
      (node (ref "C28") (pin "1") (pinfunction "1_1") (pintype "unspecified"))
      (node (ref "C30") (pin "1") (pinfunction "1_1") (pintype "unspecified"))
      (node (ref "H6") (pin "5") (pinfunction "5_5") (pintype "unspecified"))
      (node (ref "H6") (pin "6") (pinfunction "6_6") (pintype "unspecified"))
      (node (ref "H7") (pin "1") (pinfunction "1_1") (pintype "unspecified"))
      (node (ref "H7") (pin "2") (pinfunction "2_2") (pintype "unspecified"))
      (node (ref "H7") (pin "3") (pinfunction "3_3") (pintype "unspecified"))
      (node (ref "H7") (pin "4") (pinfunction "4_4") (pintype "unspecified"))
      (node (ref "R12") (pin "2") (pinfunction "2_2") (pintype "input"))
      (node (ref "R13") (pin "2") (pinfunction "2_2") (pintype "input"))
      (node (ref "R23") (pin "2") (pinfunction "2_2") (pintype "input"))
      (node (ref "R24") (pin "2") (pinfunction "2_2") (pintype "input"))
      (node (ref "R6") (pin "2") (pinfunction "2_2") (pintype "input"))
      (node (ref "U2") (pin "100") (pinfunction "VDD_3_100") (pintype "input"))
      (node (ref "U2") (pin "11") (pinfunction "VDD_5_11") (pintype "input"))
      (node (ref "U2") (pin "28") (pinfunction "VDD_4_28") (pintype "input"))
      (node (ref "U2") (pin "50") (pinfunction "VDD_1_50") (pintype "input"))
      (node (ref "U2") (pin "75") (pinfunction "VDD_2_75") (pintype "input"))
      (node (ref "U22") (pin "1") (pinfunction "1_1") (pintype "unspecified"))
      (node (ref "U30") (pin "2") (pinfunction "VOUT_2") (pintype "unspecified"))
      (node (ref "U30") (pin "4") (pinfunction "VOUT_4") (pintype "unspecified"))
      (node (ref "U33") (pin "3") (pinfunction "IO2_3") (pintype "unspecified"))
      (node (ref "U33") (pin "7") (pinfunction "IO3_7") (pintype "unspecified"))
      (node (ref "U33") (pin "8") (pinfunction "VCC_8") (pintype "unspecified"))
    )
    (net (code "79") (name "5V") (class "Default")
      (node (ref "C20") (pin "2") (pinfunction "2_2") (pintype "input"))
      (node (ref "C26") (pin "1") (pinfunction "1_1") (pintype "unspecified"))
      (node (ref "H6") (pin "1") (pinfunction "1_1") (pintype "unspecified"))
      (node (ref "H6") (pin "2") (pinfunction "2_2") (pintype "unspecified"))
      (node (ref "H6") (pin "24") (pinfunction "24_24") (pintype "unspecified"))
      (node (ref "H6") (pin "3") (pinfunction "3_3") (pintype "unspecified"))
      (node (ref "U22") (pin "10") (pinfunction "10_10") (pintype "unspecified"))
      (node (ref "U30") (pin "3") (pinfunction "VIN_3") (pintype "unspecified"))
    )
    (net (code "80") (name "BOOT0") (class "Default")
      (node (ref "H7") (pin "7") (pinfunction "7_7") (pintype "unspecified"))
      (node (ref "R21") (pin "2") (pinfunction "2_2") (pintype "input"))
      (node (ref "U2") (pin "94") (pinfunction "BOOT0_94") (pintype "input"))
    )
    (net (code "81") (name "GND") (class "Default")
      (node (ref "C11") (pin "2") (pinfunction "2_2") (pintype "unspecified"))
      (node (ref "C20") (pin "1") (pinfunction "1_1") (pintype "input"))
      (node (ref "C21") (pin "1") (pinfunction "1_1") (pintype "unspecified"))
      (node (ref "C22") (pin "1") (pinfunction "1_1") (pintype "unspecified"))
      (node (ref "C23") (pin "1") (pinfunction "1_1") (pintype "unspecified"))
      (node (ref "C24") (pin "1") (pinfunction "1_1") (pintype "unspecified"))
      (node (ref "C25") (pin "1") (pinfunction "1_1") (pintype "unspecified"))
      (node (ref "C26") (pin "2") (pinfunction "2_2") (pintype "unspecified"))
      (node (ref "C27") (pin "1") (pinfunction "1_1") (pintype "input"))
      (node (ref "C28") (pin "2") (pinfunction "2_2") (pintype "unspecified"))
      (node (ref "C29") (pin "1") (pinfunction "1_1") (pintype "unspecified"))
      (node (ref "C30") (pin "2") (pinfunction "2_2") (pintype "unspecified"))
      (node (ref "C5") (pin "2") (pinfunction "2_2") (pintype "unspecified"))
      (node (ref "C6") (pin "2") (pinfunction "2_2") (pintype "unspecified"))
      (node (ref "C7") (pin "2") (pinfunction "2_2") (pintype "input"))
      (node (ref "C8") (pin "2") (pinfunction "2_2") (pintype "input"))
      (node (ref "H6") (pin "10") (pinfunction "10_10") (pintype "unspecified"))
      (node (ref "H6") (pin "7") (pinfunction "7_7") (pintype "unspecified"))
      (node (ref "H6") (pin "8") (pinfunction "8_8") (pintype "unspecified"))
      (node (ref "H6") (pin "9") (pinfunction "9_9") (pintype "unspecified"))
      (node (ref "H7") (pin "24") (pinfunction "24_24") (pintype "unspecified"))
      (node (ref "H7") (pin "5") (pinfunction "5_5") (pintype "unspecified"))
      (node (ref "H7") (pin "6") (pinfunction "6_6") (pintype "unspecified"))
      (node (ref "LED1") (pin "1") (pinfunction "K_1") (pintype "unspecified"))
      (node (ref "LED2") (pin "1") (pinfunction "K_1") (pintype "unspecified"))
      (node (ref "R25") (pin "1") (pinfunction "1_1") (pintype "input"))
      (node (ref "R26") (pin "1") (pinfunction "1_1") (pintype "input"))
      (node (ref "R5") (pin "2") (pinfunction "2_2") (pintype "input"))
      (node (ref "RESET") (pin "1") (pinfunction "1_1") (pintype "unspecified"))
      (node (ref "U2") (pin "10") (pinfunction "VSS_5_10") (pintype "input"))
      (node (ref "U2") (pin "27") (pinfunction "VSS_4_27") (pintype "input"))
      (node (ref "U2") (pin "74") (pinfunction "VSS_2_74") (pintype "input"))
      (node (ref "U2") (pin "99") (pinfunction "VSS_3_99") (pintype "input"))
      (node (ref "U22") (pin "4") (pinfunction "4_4") (pintype "unspecified"))
      (node (ref "U22") (pin "7") (pinfunction "7_7") (pintype "unspecified"))
      (node (ref "U30") (pin "1") (pinfunction "GND_1") (pintype "unspecified"))
      (node (ref "U33") (pin "4") (pinfunction "GND_4") (pintype "unspecified"))
    )
    (net (code "82") (name "Net-(LED1-A)") (class "Default")
      (node (ref "LED1") (pin "2") (pinfunction "A_2") (pintype "unspecified"))
      (node (ref "R12") (pin "1") (pinfunction "1_1") (pintype "input"))
    )
    (net (code "83") (name "Net-(LED2-A)") (class "Default")
      (node (ref "LED2") (pin "2") (pinfunction "A_2") (pintype "unspecified"))
      (node (ref "R16") (pin "1") (pinfunction "1_1") (pintype "input"))
    )
    (net (code "84") (name "Net-(R21-Pad1)") (class "Default")
      (node (ref "R21") (pin "1") (pinfunction "1_1") (pintype "input"))
      (node (ref "R23") (pin "1") (pinfunction "1_1") (pintype "input"))
      (node (ref "R25") (pin "2") (pinfunction "2_2") (pintype "input"))
    )
    (net (code "85") (name "Net-(R22-Pad2)") (class "Default")
      (node (ref "R22") (pin "2") (pinfunction "2_2") (pintype "input"))
      (node (ref "R24") (pin "1") (pinfunction "1_1") (pintype "input"))
      (node (ref "R26") (pin "2") (pinfunction "2_2") (pintype "input"))
    )
    (net (code "86") (name "Net-(U2-OSC_IN)") (class "Default")
      (node (ref "C8") (pin "1") (pinfunction "1_1") (pintype "input"))
      (node (ref "R7") (pin "2") (pinfunction "2_2") (pintype "input"))
      (node (ref "U2") (pin "12") (pinfunction "OSC_IN_12") (pintype "input"))
      (node (ref "X3") (pin "1") (pinfunction "OSC1_1") (pintype "input"))
    )
    (net (code "87") (name "Net-(U2-OSC_OUT)") (class "Default")
      (node (ref "C7") (pin "1") (pinfunction "1_1") (pintype "input"))
      (node (ref "R7") (pin "1") (pinfunction "1_1") (pintype "input"))
      (node (ref "U2") (pin "13") (pinfunction "OSC_OUT_13") (pintype "input"))
      (node (ref "X3") (pin "2") (pinfunction "OSC2_2") (pintype "input"))
    )
    (net (code "88") (name "Net-(U2-VCAP_1)") (class "Default")
      (node (ref "C6") (pin "1") (pinfunction "1_1") (pintype "unspecified"))
      (node (ref "U2") (pin "49") (pinfunction "VCAP_1_49") (pintype "input"))
    )
    (net (code "89") (name "Net-(U2-VCAP_2)") (class "Default")
      (node (ref "C5") (pin "1") (pinfunction "1_1") (pintype "unspecified"))
      (node (ref "U2") (pin "73") (pinfunction "VCAP_2_73") (pintype "input"))
    )
    (net (code "90") (name "PA5") (class "Default")
      (node (ref "H6") (pin "19") (pinfunction "19_19") (pintype "unspecified"))
      (node (ref "U2") (pin "30") (pinfunction "PA5/ADC12_IN5/DAC_OUT2/SPI1_SCK_30") (pintype "input"))
      (node (ref "U33") (pin "6") (pinfunction "CLK_6") (pintype "unspecified"))
    )
    (net (code "91") (name "PA6") (class "Default")
      (node (ref "H6") (pin "20") (pinfunction "20_20") (pintype "unspecified"))
      (node (ref "U2") (pin "31") (pinfunction "PA6/ADC12_IN6/TIM3_CH1/TIM8_BKIN/SPI1_MISO/(TIM1_BKIN)_31") (pintype "input"))
      (node (ref "U33") (pin "2") (pinfunction "DO_2") (pintype "unspecified"))
    )
    (net (code "92") (name "PA7") (class "Default")
      (node (ref "H6") (pin "21") (pinfunction "21_21") (pintype "unspecified"))
      (node (ref "U2") (pin "32") (pinfunction "PA7/ADC12_IN7/TIM3_CH2/TIM8_CH1N/SPI1_MOSI(TIM1_CH1N)_32") (pintype "input"))
      (node (ref "U33") (pin "5") (pinfunction "DI_5") (pintype "unspecified"))
    )
    (net (code "93") (name "PA8") (class "Default")
      (node (ref "R16") (pin "2") (pinfunction "2_2") (pintype "input"))
      (node (ref "U2") (pin "67") (pinfunction "PA8/USART1_CK/TIM1_CH1/MCO_67") (pintype "input"))
    )
    (net (code "94") (name "PB2{slash}BOOT1") (class "Default")
      (node (ref "H7") (pin "8") (pinfunction "8_8") (pintype "unspecified"))
      (node (ref "R22") (pin "1") (pinfunction "1_1") (pintype "input"))
      (node (ref "U2") (pin "37") (pinfunction "BOOT1/PB2_37") (pintype "input"))
    )
    (net (code "95") (name "PB12") (class "Default")
      (node (ref "H6") (pin "23") (pinfunction "23_23") (pintype "unspecified"))
      (node (ref "U2") (pin "51") (pinfunction "SPI2_NSS/I2S2_WS/I2S2_SMBA1/TIM1_BKIN/USART3_CK/PB12_51") (pintype "input"))
      (node (ref "U33") (pin "1") (pinfunction "CS#_1") (pintype "unspecified"))
    )
    (net (code "96") (name "RST") (class "Default")
      (node (ref "C29") (pin "2") (pinfunction "2_2") (pintype "unspecified"))
      (node (ref "H6") (pin "4") (pinfunction "4_4") (pintype "unspecified"))
      (node (ref "R13") (pin "1") (pinfunction "1_1") (pintype "input"))
      (node (ref "RESET") (pin "2") (pinfunction "2_2") (pintype "unspecified"))
      (node (ref "U2") (pin "14") (pinfunction "NRST_14") (pintype "input"))
      (node (ref "U22") (pin "9") (pinfunction "9_9") (pintype "unspecified"))
    )
    (net (code "97") (name "VDDA") (class "Default")
      (node (ref "C10") (pin "2") (pinfunction "2_2") (pintype "unspecified"))
      (node (ref "C9") (pin "2") (pinfunction "2_2") (pintype "input"))
      (node (ref "R4") (pin "2") (pinfunction "2_2") (pintype "input"))
      (node (ref "R6") (pin "1") (pinfunction "1_1") (pintype "input"))
      (node (ref "U2") (pin "19") (pinfunction "VDD_19") (pintype "input"))
      (node (ref "U2") (pin "22") (pinfunction "VDDA_22") (pintype "input"))
    )
    (net (code "98") (name "unconnected-(U22-Pad8)") (class "Default")
      (node (ref "U22") (pin "8") (pinfunction "8_8") (pintype "unspecified+no_connect"))
    )
  )
)
